# MagnetCard.net
KiCad netlist of a schematic drawn in EAGLE
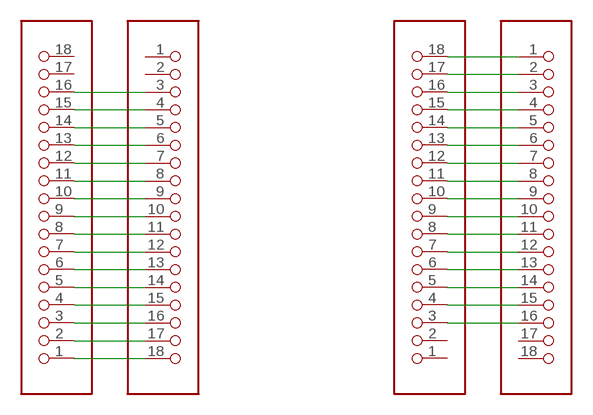
[diagram p0: schematic, sheet 1]

(export (version "E")
  (design (tool "Eeschema 10.0.6"))
  (components
    (comp (ref "U$1")
      (value "18X1_CARD_PADLONG")
      (footprint "eagle-import:18X1_CARDPAD_LONG")
      (libsource (lib "eagle-import") (part "18X1_CARD_PADLONG"))
    )
    (comp (ref "U$2")
      (value "18X1_CARD_PADLONG")
      (footprint "eagle-import:18X1_CARDPAD_LONG")
      (libsource (lib "eagle-import") (part "18X1_CARD_PADLONG"))
    )
    (comp (ref "U$3")
      (value "18X1_CARD_PADLONG")
      (footprint "eagle-import:18X1_CARDPAD_LONG")
      (libsource (lib "eagle-import") (part "18X1_CARD_PADLONG"))
    )
    (comp (ref "U$4")
      (value "18X1_CARD_PADLONG")
      (footprint "eagle-import:18X1_CARDPAD_LONG")
      (libsource (lib "eagle-import") (part "18X1_CARD_PADLONG"))
    )
  )
  (nets
    (net (code "1") (name "Net-(U$1-Pad3)") (class "Default")
      (node (ref "U$1") (pin "3") (pinfunction "3_3") (pintype "bidirectional"))
      (node (ref "U$2") (pin "16") (pinfunction "16_16") (pintype "bidirectional"))
    )
    (net (code "2") (name "Net-(U$1-Pad4)") (class "Default")
      (node (ref "U$1") (pin "4") (pinfunction "4_4") (pintype "bidirectional"))
      (node (ref "U$2") (pin "15") (pinfunction "15_15") (pintype "bidirectional"))
    )
    (net (code "3") (name "Net-(U$1-Pad5)") (class "Default")
      (node (ref "U$1") (pin "5") (pinfunction "5_5") (pintype "bidirectional"))
      (node (ref "U$2") (pin "14") (pinfunction "14_14") (pintype "bidirectional"))
    )
    (net (code "4") (name "Net-(U$1-Pad6)") (class "Default")
      (node (ref "U$1") (pin "6") (pinfunction "6_6") (pintype "bidirectional"))
      (node (ref "U$2") (pin "13") (pinfunction "13_13") (pintype "bidirectional"))
    )
    (net (code "5") (name "Net-(U$1-Pad7)") (class "Default")
      (node (ref "U$1") (pin "7") (pinfunction "7_7") (pintype "bidirectional"))
      (node (ref "U$2") (pin "12") (pinfunction "12_12") (pintype "bidirectional"))
    )
    (net (code "6") (name "Net-(U$1-Pad8)") (class "Default")
      (node (ref "U$1") (pin "8") (pinfunction "8_8") (pintype "bidirectional"))
      (node (ref "U$2") (pin "11") (pinfunction "11_11") (pintype "bidirectional"))
    )
    (net (code "7") (name "Net-(U$1-Pad9)") (class "Default")
      (node (ref "U$1") (pin "9") (pinfunction "9_9") (pintype "bidirectional"))
      (node (ref "U$2") (pin "10") (pinfunction "10_10") (pintype "bidirectional"))
    )
    (net (code "8") (name "Net-(U$1-Pad10)") (class "Default")
      (node (ref "U$1") (pin "10") (pinfunction "10_10") (pintype "bidirectional"))
      (node (ref "U$2") (pin "9") (pinfunction "9_9") (pintype "bidirectional"))
    )
    (net (code "9") (name "Net-(U$1-Pad11)") (class "Default")
      (node (ref "U$1") (pin "11") (pinfunction "11_11") (pintype "bidirectional"))
      (node (ref "U$2") (pin "8") (pinfunction "8_8") (pintype "bidirectional"))
    )
    (net (code "10") (name "Net-(U$1-Pad12)") (class "Default")
      (node (ref "U$1") (pin "12") (pinfunction "12_12") (pintype "bidirectional"))
      (node (ref "U$2") (pin "7") (pinfunction "7_7") (pintype "bidirectional"))
    )
    (net (code "11") (name "Net-(U$1-Pad13)") (class "Default")
      (node (ref "U$1") (pin "13") (pinfunction "13_13") (pintype "bidirectional"))
      (node (ref "U$2") (pin "6") (pinfunction "6_6") (pintype "bidirectional"))
    )
    (net (code "12") (name "Net-(U$1-Pad14)") (class "Default")
      (node (ref "U$1") (pin "14") (pinfunction "14_14") (pintype "bidirectional"))
      (node (ref "U$2") (pin "5") (pinfunction "5_5") (pintype "bidirectional"))
    )
    (net (code "13") (name "Net-(U$1-Pad15)") (class "Default")
      (node (ref "U$1") (pin "15") (pinfunction "15_15") (pintype "bidirectional"))
      (node (ref "U$2") (pin "4") (pinfunction "4_4") (pintype "bidirectional"))
    )
    (net (code "14") (name "Net-(U$1-Pad16)") (class "Default")
      (node (ref "U$1") (pin "16") (pinfunction "16_16") (pintype "bidirectional"))
      (node (ref "U$2") (pin "3") (pinfunction "3_3") (pintype "bidirectional"))
    )
    (net (code "15") (name "Net-(U$1-Pad17)") (class "Default")
      (node (ref "U$1") (pin "17") (pinfunction "17_17") (pintype "bidirectional"))
      (node (ref "U$2") (pin "2") (pinfunction "2_2") (pintype "bidirectional"))
    )
    (net (code "16") (name "Net-(U$1-Pad18)") (class "Default")
      (node (ref "U$1") (pin "18") (pinfunction "18_18") (pintype "bidirectional"))
      (node (ref "U$2") (pin "1") (pinfunction "1_1") (pintype "bidirectional"))
    )
    (net (code "17") (name "Net-(U$3-Pad1)") (class "Default")
      (node (ref "U$3") (pin "1") (pinfunction "1_1") (pintype "bidirectional"))
      (node (ref "U$4") (pin "18") (pinfunction "18_18") (pintype "bidirectional"))
    )
    (net (code "18") (name "Net-(U$3-Pad2)") (class "Default")
      (node (ref "U$3") (pin "2") (pinfunction "2_2") (pintype "bidirectional"))
      (node (ref "U$4") (pin "17") (pinfunction "17_17") (pintype "bidirectional"))
    )
    (net (code "19") (name "Net-(U$3-Pad3)") (class "Default")
      (node (ref "U$3") (pin "3") (pinfunction "3_3") (pintype "bidirectional"))
      (node (ref "U$4") (pin "16") (pinfunction "16_16") (pintype "bidirectional"))
    )
    (net (code "20") (name "Net-(U$3-Pad4)") (class "Default")
      (node (ref "U$3") (pin "4") (pinfunction "4_4") (pintype "bidirectional"))
      (node (ref "U$4") (pin "15") (pinfunction "15_15") (pintype "bidirectional"))
    )
    (net (code "21") (name "Net-(U$3-Pad5)") (class "Default")
      (node (ref "U$3") (pin "5") (pinfunction "5_5") (pintype "bidirectional"))
      (node (ref "U$4") (pin "14") (pinfunction "14_14") (pintype "bidirectional"))
    )
    (net (code "22") (name "Net-(U$3-Pad6)") (class "Default")
      (node (ref "U$3") (pin "6") (pinfunction "6_6") (pintype "bidirectional"))
      (node (ref "U$4") (pin "13") (pinfunction "13_13") (pintype "bidirectional"))
    )
    (net (code "23") (name "Net-(U$3-Pad7)") (class "Default")
      (node (ref "U$3") (pin "7") (pinfunction "7_7") (pintype "bidirectional"))
      (node (ref "U$4") (pin "12") (pinfunction "12_12") (pintype "bidirectional"))
    )
    (net (code "24") (name "Net-(U$3-Pad8)") (class "Default")
      (node (ref "U$3") (pin "8") (pinfunction "8_8") (pintype "bidirectional"))
      (node (ref "U$4") (pin "11") (pinfunction "11_11") (pintype "bidirectional"))
    )
    (net (code "25") (name "Net-(U$3-Pad9)") (class "Default")
      (node (ref "U$3") (pin "9") (pinfunction "9_9") (pintype "bidirectional"))
      (node (ref "U$4") (pin "10") (pinfunction "10_10") (pintype "bidirectional"))
    )
    (net (code "26") (name "Net-(U$3-Pad10)") (class "Default")
      (node (ref "U$3") (pin "10") (pinfunction "10_10") (pintype "bidirectional"))
      (node (ref "U$4") (pin "9") (pinfunction "9_9") (pintype "bidirectional"))
    )
    (net (code "27") (name "Net-(U$3-Pad11)") (class "Default")
      (node (ref "U$3") (pin "11") (pinfunction "11_11") (pintype "bidirectional"))
      (node (ref "U$4") (pin "8") (pinfunction "8_8") (pintype "bidirectional"))
    )
    (net (code "28") (name "Net-(U$3-Pad12)") (class "Default")
      (node (ref "U$3") (pin "12") (pinfunction "12_12") (pintype "bidirectional"))
      (node (ref "U$4") (pin "7") (pinfunction "7_7") (pintype "bidirectional"))
    )
    (net (code "29") (name "Net-(U$3-Pad13)") (class "Default")
      (node (ref "U$3") (pin "13") (pinfunction "13_13") (pintype "bidirectional"))
      (node (ref "U$4") (pin "6") (pinfunction "6_6") (pintype "bidirectional"))
    )
    (net (code "30") (name "Net-(U$3-Pad14)") (class "Default")
      (node (ref "U$3") (pin "14") (pinfunction "14_14") (pintype "bidirectional"))
      (node (ref "U$4") (pin "5") (pinfunction "5_5") (pintype "bidirectional"))
    )
    (net (code "31") (name "Net-(U$3-Pad15)") (class "Default")
      (node (ref "U$3") (pin "15") (pinfunction "15_15") (pintype "bidirectional"))
      (node (ref "U$4") (pin "4") (pinfunction "4_4") (pintype "bidirectional"))
    )
    (net (code "32") (name "Net-(U$3-Pad16)") (class "Default")
      (node (ref "U$3") (pin "16") (pinfunction "16_16") (pintype "bidirectional"))
      (node (ref "U$4") (pin "3") (pinfunction "3_3") (pintype "bidirectional"))
    )
    (net (code "33") (name "unconnected-(U$1-Pad1)") (class "Default")
      (node (ref "U$1") (pin "1") (pinfunction "1_1") (pintype "bidirectional"))
    )
    (net (code "34") (name "unconnected-(U$1-Pad2)") (class "Default")
      (node (ref "U$1") (pin "2") (pinfunction "2_2") (pintype "bidirectional"))
    )
    (net (code "35") (name "unconnected-(U$2-Pad17)") (class "Default")
      (node (ref "U$2") (pin "17") (pinfunction "17_17") (pintype "bidirectional"))
    )
    (net (code "36") (name "unconnected-(U$2-Pad18)") (class "Default")
      (node (ref "U$2") (pin "18") (pinfunction "18_18") (pintype "bidirectional"))
    )
    (net (code "37") (name "unconnected-(U$3-Pad17)") (class "Default")
      (node (ref "U$3") (pin "17") (pinfunction "17_17") (pintype "bidirectional"))
    )
    (net (code "38") (name "unconnected-(U$3-Pad18)") (class "Default")
      (node (ref "U$3") (pin "18") (pinfunction "18_18") (pintype "bidirectional"))
    )
    (net (code "39") (name "unconnected-(U$4-Pad1)") (class "Default")
      (node (ref "U$4") (pin "1") (pinfunction "1_1") (pintype "bidirectional"))
    )
    (net (code "40") (name "unconnected-(U$4-Pad2)") (class "Default")
      (node (ref "U$4") (pin "2") (pinfunction "2_2") (pintype "bidirectional"))
    )
  )
)
